# RECEPTOR_AIS_FI_R00.net
KiCad netlist of a schematic drawn in Altium Designer
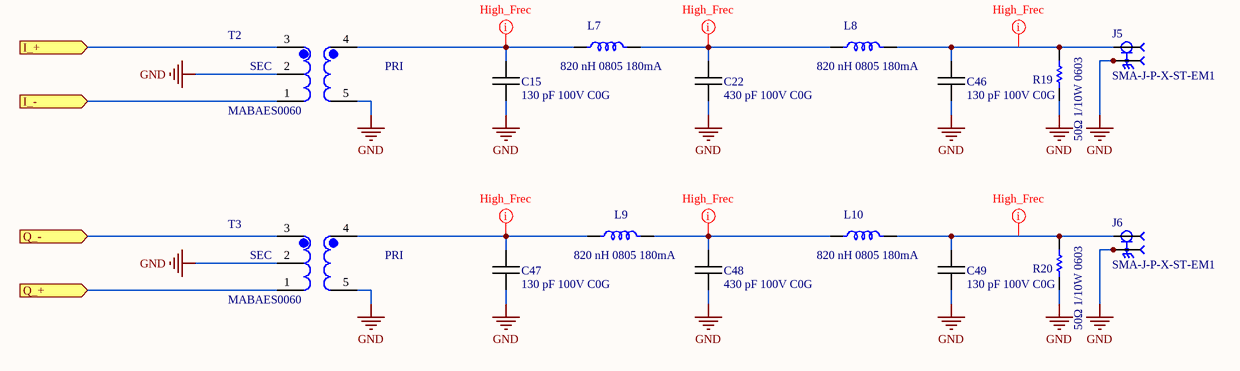
[diagram p0: RECEPTOR_AIS_FI_R00.SchDoc]

(export (version "E")
  (design (tool "Eeschema 10.0.6"))
  (components
    (comp (ref "C15")
      (value "130 pF 100V C0G")
      (footprint "C_0603")
      (description "130 pF ±1% 100V Ceramic Capacitor C0G, NP0 0603 (1608 Metric)")
      (libsource (lib "RECEPTOR_AIS_R00") (part "Capacitor NP"))
    )
    (comp (ref "C22")
      (value "430 pF 100V C0G")
      (footprint "C_0603")
      (description "430 pF ±5% 100V Ceramic Capacitor C0G, NP0 0603 (1608 Metric)")
      (libsource (lib "RECEPTOR_AIS_R00") (part "Capacitor NP"))
    )
    (comp (ref "C46")
      (value "130 pF 100V C0G")
      (footprint "C_0603")
      (description "130 pF ±1% 100V Ceramic Capacitor C0G, NP0 0603 (1608 Metric)")
      (libsource (lib "RECEPTOR_AIS_R00") (part "Capacitor NP"))
    )
    (comp (ref "C47")
      (value "130 pF 100V C0G")
      (footprint "C_0603")
      (description "130 pF ±1% 100V Ceramic Capacitor C0G, NP0 0603 (1608 Metric)")
      (libsource (lib "RECEPTOR_AIS_R00") (part "Capacitor NP"))
    )
    (comp (ref "C48")
      (value "430 pF 100V C0G")
      (footprint "C_0603")
      (description "430 pF ±5% 100V Ceramic Capacitor C0G, NP0 0603 (1608 Metric)")
      (libsource (lib "RECEPTOR_AIS_R00") (part "Capacitor NP"))
    )
    (comp (ref "C49")
      (value "130 pF 100V C0G")
      (footprint "C_0603")
      (description "130 pF ±1% 100V Ceramic Capacitor C0G, NP0 0603 (1608 Metric)")
      (libsource (lib "RECEPTOR_AIS_R00") (part "Capacitor NP"))
    )
    (comp (ref "J5")
      (value "SMA-J-P-X-ST-EM1")
      (footprint "CONN_SMA-J-P-H-ST-EM1_SAI")
      (description "SMA Connector Jack, Female Socket 50 Ohms Board Edge, Cutout; Surface Mount Solder")
      (fields (field (name "MF") "Samtec") (field (name "MP") "SMA-J-P-H-ST-EM3"))
      (libsource (lib "RECEPTOR_AIS_R00") (part "SMA-J-P-X-ST-EM1"))
    )
    (comp (ref "J6")
      (value "SMA-J-P-X-ST-EM1")
      (footprint "CONN_SMA-J-P-H-ST-EM1_SAI")
      (description "SMA Connector Jack, Female Socket 50 Ohms Board Edge, Cutout; Surface Mount Solder")
      (fields (field (name "MF") "Samtec") (field (name "MP") "SMA-J-P-H-ST-EM3"))
      (libsource (lib "RECEPTOR_AIS_R00") (part "SMA-J-P-X-ST-EM1"))
    )
    (comp (ref "L7")
      (value "820 nH 0805 180mA")
      (footprint "L_0805")
      (description "FIXED IND 820NH 180MA 2.35 OHM")
      (libsource (lib "RECEPTOR_AIS_R00") (part "IND"))
    )
    (comp (ref "L8")
      (value "820 nH 0805 180mA")
      (footprint "L_0805")
      (description "FIXED IND 820NH 180MA 2.35 OHM")
      (libsource (lib "RECEPTOR_AIS_R00") (part "IND"))
    )
    (comp (ref "L9")
      (value "820 nH 0805 180mA")
      (footprint "L_0805")
      (description "FIXED IND 820NH 180MA 2.35 OHM")
      (libsource (lib "RECEPTOR_AIS_R00") (part "IND"))
    )
    (comp (ref "L10")
      (value "820 nH 0805 180mA")
      (footprint "L_0805")
      (description "FIXED IND 820NH 180MA 2.35 OHM")
      (libsource (lib "RECEPTOR_AIS_R00") (part "IND"))
    )
    (comp (ref "R19")
      (value "50Ω 1/10W 0603")
      (footprint "R_0603")
      (description "50 Ohms ±0.1% 0.1W, 1/10W Chip Resistor 0603 (1608 Metric) Thin Film")
      (libsource (lib "RECEPTOR_AIS_R00") (part "Res1"))
    )
    (comp (ref "R20")
      (value "50Ω 1/10W 0603")
      (footprint "R_0603")
      (description "50 Ohms ±0.1% 0.1W, 1/10W Chip Resistor 0603 (1608 Metric) Thin Film")
      (libsource (lib "RECEPTOR_AIS_R00") (part "Res1"))
    )
    (comp (ref "T2")
      (value "MABAES0060")
      (footprint "MABAES0060_MCM")
      (description "RF Balun 300kHz ~ 200MHz 1:1 6-SMD (5 Leads), Flat Lead")
      (fields (field (name "MF") "Mini-Circuits") (field (name "MP") "ADT1-6T+"))
      (libsource (lib "RECEPTOR_AIS_R00") (part "MABAES0060"))
    )
    (comp (ref "T3")
      (value "MABAES0060")
      (footprint "MABAES0060_MCM")
      (description "RF Balun 300kHz ~ 200MHz 1:1 6-SMD (5 Leads), Flat Lead")
      (fields (field (name "MF") "Mini-Circuits") (field (name "MP") "ADT1-6T+"))
      (libsource (lib "RECEPTOR_AIS_R00") (part "MABAES0060"))
    )
  )
  (nets
    (net (code "1") (name "/I_+") (class "Default")
      (node (ref "T2") (pin "3") (pinfunction "3_3") (pintype "passive"))
    )
    (net (code "2") (name "/I_-") (class "Default")
      (node (ref "T2") (pin "1") (pinfunction "1_1") (pintype "passive"))
    )
    (net (code "3") (name "/Q_+") (class "Default")
      (node (ref "T3") (pin "1") (pinfunction "1_1") (pintype "passive"))
    )
    (net (code "4") (name "/Q_-") (class "Default")
      (node (ref "T3") (pin "3") (pinfunction "3_3") (pintype "passive"))
    )
    (net (code "5") (name "GND") (class "Default")
      (node (ref "C15") (pin "1") (pinfunction "1_1") (pintype "passive"))
      (node (ref "C22") (pin "1") (pinfunction "1_1") (pintype "passive"))
      (node (ref "C46") (pin "1") (pinfunction "1_1") (pintype "passive"))
      (node (ref "C47") (pin "1") (pinfunction "1_1") (pintype "passive"))
      (node (ref "C48") (pin "1") (pinfunction "1_1") (pintype "passive"))
      (node (ref "C49") (pin "1") (pinfunction "1_1") (pintype "passive"))
      (node (ref "J5") (pin "2") (pinfunction "2_2") (pintype "passive"))
      (node (ref "J5") (pin "3") (pinfunction "2_3") (pintype "passive"))
      (node (ref "J6") (pin "2") (pinfunction "2_2") (pintype "passive"))
      (node (ref "J6") (pin "3") (pinfunction "2_3") (pintype "passive"))
      (node (ref "R19") (pin "1") (pinfunction "1_1") (pintype "passive"))
      (node (ref "R20") (pin "1") (pinfunction "1_1") (pintype "passive"))
      (node (ref "T2") (pin "2") (pinfunction "2_2") (pintype "passive"))
      (node (ref "T2") (pin "5") (pinfunction "5_5") (pintype "passive"))
      (node (ref "T3") (pin "2") (pinfunction "2_2") (pintype "passive"))
      (node (ref "T3") (pin "5") (pinfunction "5_5") (pintype "passive"))
    )
    (net (code "6") (name "Net-(C15-Pad2)") (class "Default")
      (node (ref "C15") (pin "2") (pinfunction "2_2") (pintype "passive"))
      (node (ref "L7") (pin "1") (pinfunction "1_1") (pintype "passive"))
      (node (ref "T2") (pin "4") (pinfunction "4_4") (pintype "passive"))
    )
    (net (code "7") (name "Net-(C22-Pad2)") (class "Default")
      (node (ref "C22") (pin "2") (pinfunction "2_2") (pintype "passive"))
      (node (ref "L7") (pin "2") (pinfunction "2_2") (pintype "passive"))
      (node (ref "L8") (pin "1") (pinfunction "1_1") (pintype "passive"))
    )
    (net (code "8") (name "Net-(C46-Pad2)") (class "Default")
      (node (ref "C46") (pin "2") (pinfunction "2_2") (pintype "passive"))
      (node (ref "J5") (pin "1") (pinfunction "1_1") (pintype "passive"))
      (node (ref "L8") (pin "2") (pinfunction "2_2") (pintype "passive"))
      (node (ref "R19") (pin "2") (pinfunction "2_2") (pintype "passive"))
    )
    (net (code "9") (name "Net-(C47-Pad2)") (class "Default")
      (node (ref "C47") (pin "2") (pinfunction "2_2") (pintype "passive"))
      (node (ref "L9") (pin "1") (pinfunction "1_1") (pintype "passive"))
      (node (ref "T3") (pin "4") (pinfunction "4_4") (pintype "passive"))
    )
    (net (code "10") (name "Net-(C48-Pad2)") (class "Default")
      (node (ref "C48") (pin "2") (pinfunction "2_2") (pintype "passive"))
      (node (ref "L10") (pin "1") (pinfunction "1_1") (pintype "passive"))
      (node (ref "L9") (pin "2") (pinfunction "2_2") (pintype "passive"))
    )
    (net (code "11") (name "Net-(C49-Pad2)") (class "Default")
      (node (ref "C49") (pin "2") (pinfunction "2_2") (pintype "passive"))
      (node (ref "J6") (pin "1") (pinfunction "1_1") (pintype "passive"))
      (node (ref "L10") (pin "2") (pinfunction "2_2") (pintype "passive"))
      (node (ref "R20") (pin "2") (pinfunction "2_2") (pintype "passive"))
    )
  )
)
